# IQInput.net
KiCad netlist of a schematic drawn in EAGLE
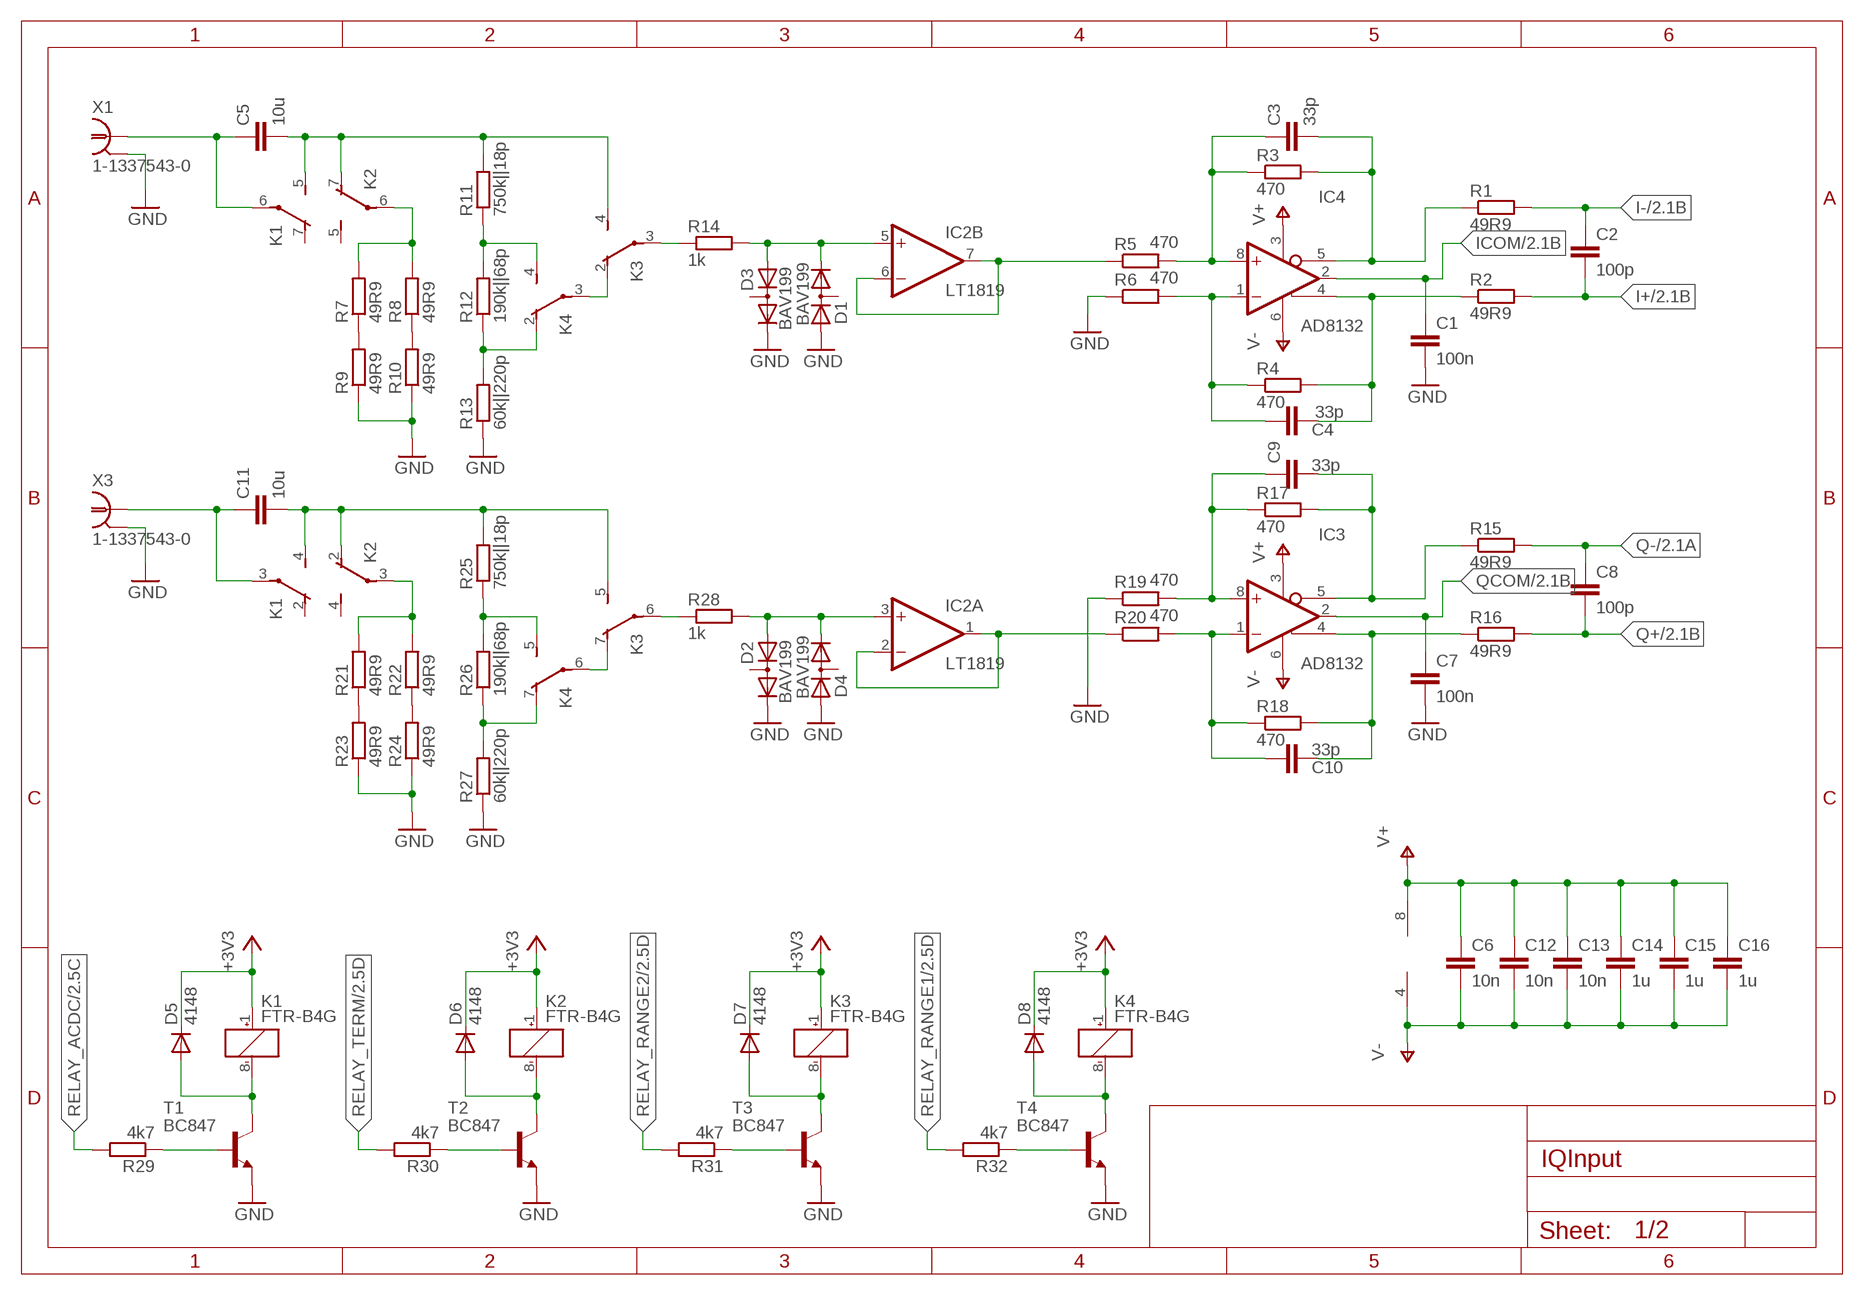
[diagram p0: schematic, sheet 1]
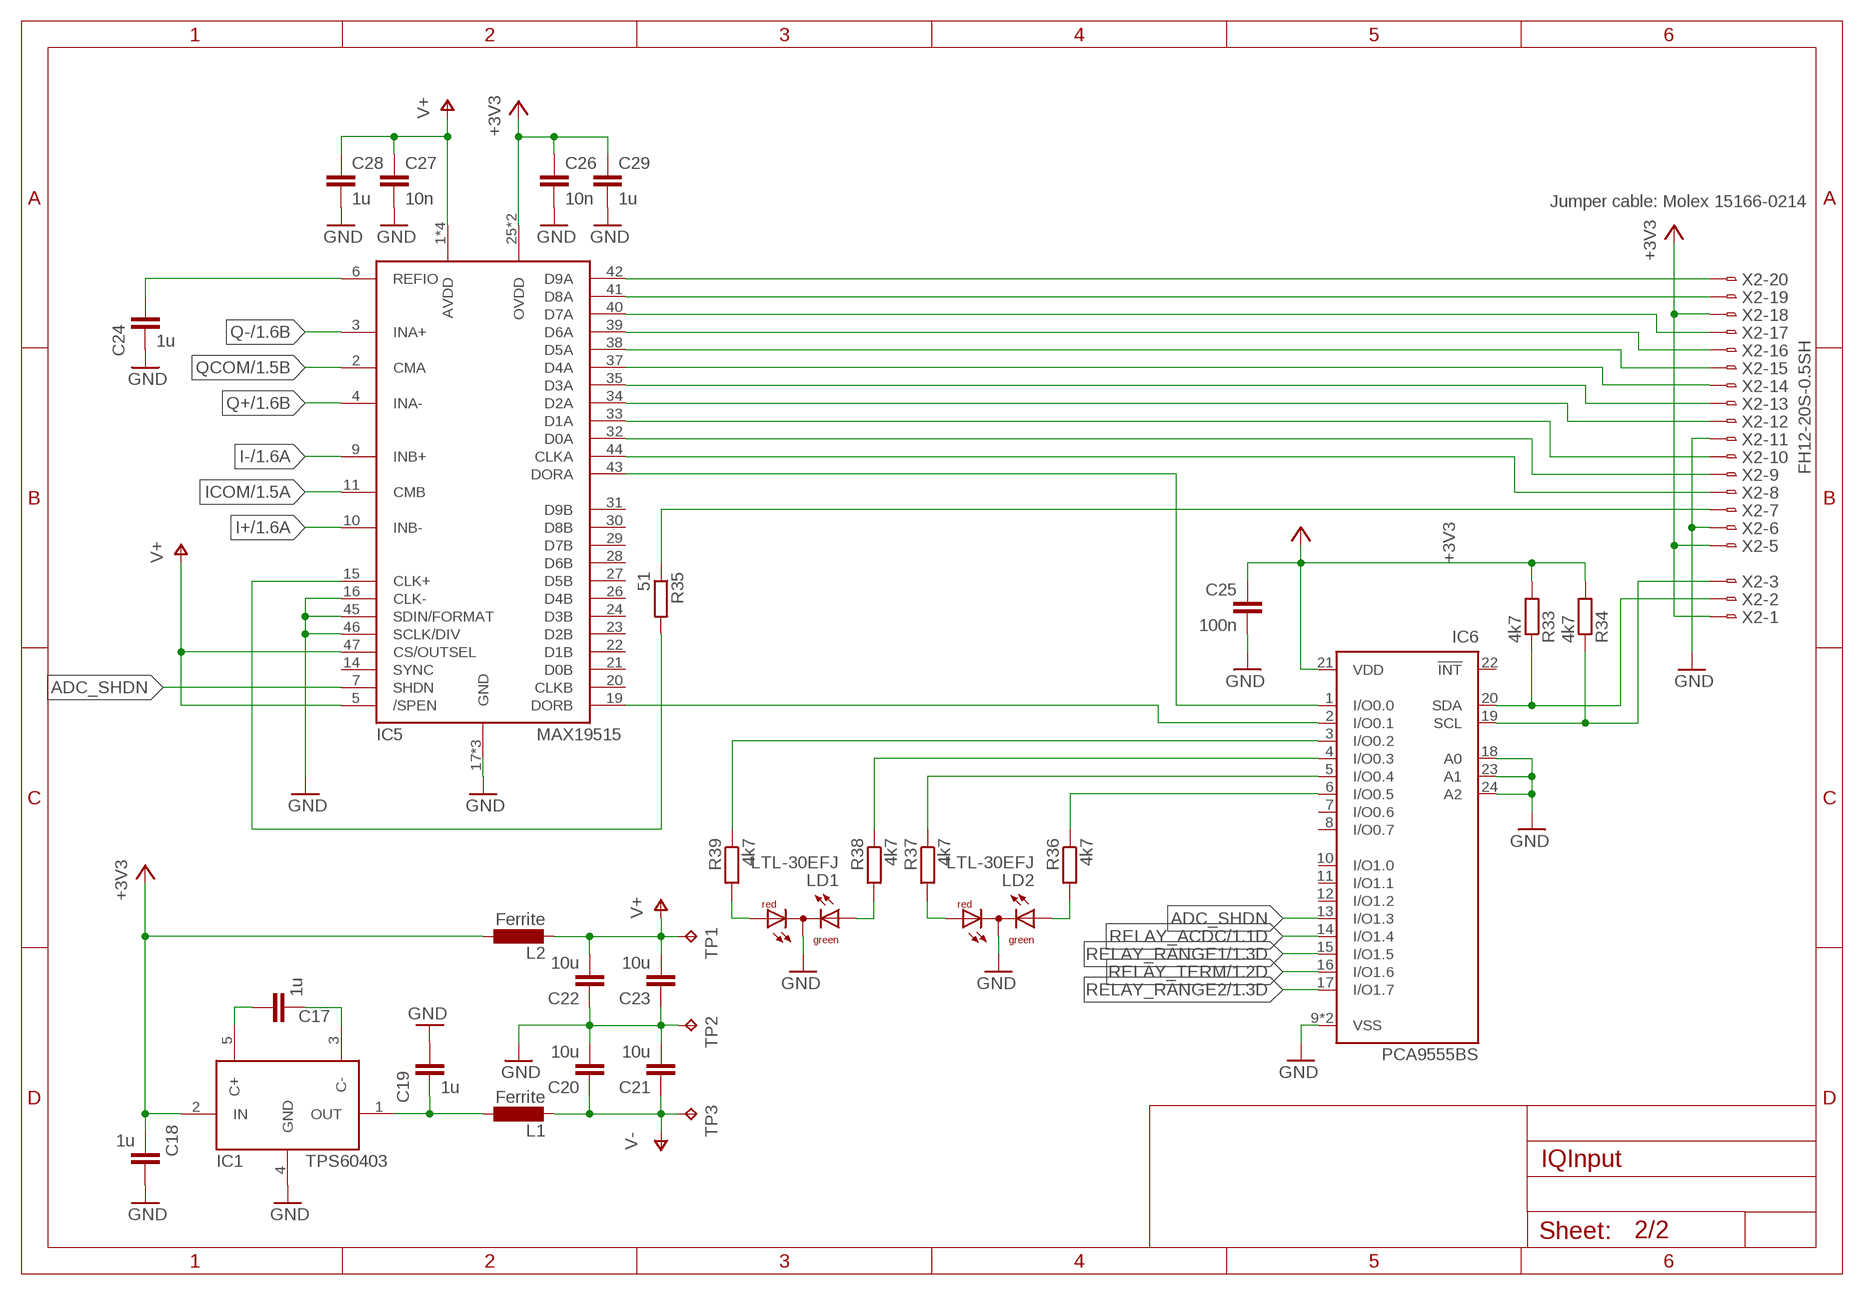
[diagram p1: schematic, sheet 2]

(export (version "E")
  (design (tool "Eeschema 10.0.6"))
  (components
    (comp (ref "C17")
      (value "1u")
      (footprint "eagle-import:C0603")
      (libsource (lib "eagle-import") (part "C-EUC0603"))
    )
    (comp (ref "C18")
      (value "1u")
      (footprint "eagle-import:C0603")
      (libsource (lib "eagle-import") (part "C-EUC0603"))
    )
    (comp (ref "C19")
      (value "1u")
      (footprint "eagle-import:C0603")
      (libsource (lib "eagle-import") (part "C-EUC0603"))
    )
    (comp (ref "C20")
      (value "10u")
      (footprint "eagle-import:C1206")
      (libsource (lib "eagle-import") (part "C-EUC1206"))
    )
    (comp (ref "C21")
      (value "10u")
      (footprint "eagle-import:C1206")
      (libsource (lib "eagle-import") (part "C-EUC1206"))
    )
    (comp (ref "C22")
      (value "10u")
      (footprint "eagle-import:C1206")
      (libsource (lib "eagle-import") (part "C-EUC1206"))
    )
    (comp (ref "C23")
      (value "10u")
      (footprint "eagle-import:C1206")
      (libsource (lib "eagle-import") (part "C-EUC1206"))
    )
    (comp (ref "C24")
      (value "1u")
      (footprint "eagle-import:C0603")
      (libsource (lib "eagle-import") (part "C-EUC0603"))
    )
    (comp (ref "C25")
      (value "100n")
      (footprint "eagle-import:C0603")
      (libsource (lib "eagle-import") (part "C-EUC0603"))
    )
    (comp (ref "C26")
      (value "10n")
      (footprint "eagle-import:C0603")
      (libsource (lib "eagle-import") (part "C-EUC0603"))
    )
    (comp (ref "C27")
      (value "10n")
      (footprint "eagle-import:C0603")
      (libsource (lib "eagle-import") (part "C-EUC0603"))
    )
    (comp (ref "C28")
      (value "1u")
      (footprint "eagle-import:C0603")
      (libsource (lib "eagle-import") (part "C-EUC0603"))
    )
    (comp (ref "C29")
      (value "1u")
      (footprint "eagle-import:C0603")
      (libsource (lib "eagle-import") (part "C-EUC0603"))
    )
    (comp (ref "IC1")
      (value "TPS60403")
      (footprint "eagle-import:SOT23-5")
      (libsource (lib "eagle-import") (part "TPS60403"))
    )
    (comp (ref "IC5")
      (value "MAX19515")
      (footprint "eagle-import:QFN50P700X700X75-49T550N")
      (libsource (lib "eagle-import") (part "MAX19515"))
    )
    (comp (ref "IC6")
      (value "PCA9555BS")
      (footprint "eagle-import:HVQFN24")
      (fields (field (name "MPN") "PCA9555BS,118"))
      (libsource (lib "eagle-import") (part "PCA9555BS"))
    )
    (comp (ref "L1")
      (value "Ferrite")
      (footprint "eagle-import:L2012C")
      (libsource (lib "eagle-import") (part "L-EUL2012C"))
    )
    (comp (ref "L2")
      (value "Ferrite")
      (footprint "eagle-import:L2012C")
      (libsource (lib "eagle-import") (part "L-EUL2012C"))
    )
    (comp (ref "LD1")
      (value "LTL-30EFJ")
      (footprint "eagle-import:DUOLED-C-5MM")
      (libsource (lib "eagle-import") (part "DUOLED-RG-C"))
    )
    (comp (ref "LD2")
      (value "LTL-30EFJ")
      (footprint "eagle-import:DUOLED-C-5MM")
      (libsource (lib "eagle-import") (part "DUOLED-RG-C"))
    )
    (comp (ref "R33")
      (value "4k7")
      (footprint "eagle-import:R0603")
      (libsource (lib "eagle-import") (part "R-EU_R0603"))
    )
    (comp (ref "R34")
      (value "4k7")
      (footprint "eagle-import:R0603")
      (libsource (lib "eagle-import") (part "R-EU_R0603"))
    )
    (comp (ref "R35")
      (value "51")
      (footprint "eagle-import:R0603")
      (libsource (lib "eagle-import") (part "R-EU_R0603"))
    )
    (comp (ref "R36")
      (value "4k7")
      (footprint "eagle-import:R0603")
      (libsource (lib "eagle-import") (part "R-EU_R0603"))
    )
    (comp (ref "R37")
      (value "4k7")
      (footprint "eagle-import:R0603")
      (libsource (lib "eagle-import") (part "R-EU_R0603"))
    )
    (comp (ref "R38")
      (value "4k7")
      (footprint "eagle-import:R0603")
      (libsource (lib "eagle-import") (part "R-EU_R0603"))
    )
    (comp (ref "R39")
      (value "4k7")
      (footprint "eagle-import:R0603")
      (libsource (lib "eagle-import") (part "R-EU_R0603"))
    )
    (comp (ref "TP1")
      (value "TPTP15R")
      (footprint "eagle-import:TP15R")
      (libsource (lib "eagle-import") (part "TPTP15R"))
    )
    (comp (ref "TP2")
      (value "TPTP15R")
      (footprint "eagle-import:TP15R")
      (libsource (lib "eagle-import") (part "TPTP15R"))
    )
    (comp (ref "TP3")
      (value "TPTP15R")
      (footprint "eagle-import:TP15R")
      (libsource (lib "eagle-import") (part "TPTP15R"))
    )
    (comp (ref "X2")
      (value "FH12-20S-0.5SH")
      (footprint "eagle-import:FH12-20S-0.5SH")
      (fields (field (name "MPN") "FH12-20S-0.5SH(55)"))
      (libsource (lib "eagle-import") (part "FH12-20S-0.5SH"))
    )
    (comp (ref "C1")
      (value "100n")
      (footprint "eagle-import:C0603")
      (libsource (lib "eagle-import") (part "C-EUC0603"))
    )
    (comp (ref "C2")
      (value "100p")
      (footprint "eagle-import:C0603")
      (libsource (lib "eagle-import") (part "C-EUC0603"))
    )
    (comp (ref "C3")
      (value "33p")
      (footprint "eagle-import:C0603")
      (libsource (lib "eagle-import") (part "C-EUC0603"))
    )
    (comp (ref "C4")
      (value "33p")
      (footprint "eagle-import:C0603")
      (libsource (lib "eagle-import") (part "C-EUC0603"))
    )
    (comp (ref "C5")
      (value "10u")
      (footprint "eagle-import:C1206")
      (libsource (lib "eagle-import") (part "C-EUC1206"))
    )
    (comp (ref "C6")
      (value "10n")
      (footprint "eagle-import:C0603")
      (libsource (lib "eagle-import") (part "C-EUC0603"))
    )
    (comp (ref "C7")
      (value "100n")
      (footprint "eagle-import:C0603")
      (libsource (lib "eagle-import") (part "C-EUC0603"))
    )
    (comp (ref "C8")
      (value "100p")
      (footprint "eagle-import:C0603")
      (libsource (lib "eagle-import") (part "C-EUC0603"))
    )
    (comp (ref "C9")
      (value "33p")
      (footprint "eagle-import:C0603")
      (libsource (lib "eagle-import") (part "C-EUC0603"))
    )
    (comp (ref "C10")
      (value "33p")
      (footprint "eagle-import:C0603")
      (libsource (lib "eagle-import") (part "C-EUC0603"))
    )
    (comp (ref "C11")
      (value "10u")
      (footprint "eagle-import:C1206")
      (libsource (lib "eagle-import") (part "C-EUC1206"))
    )
    (comp (ref "C12")
      (value "10n")
      (footprint "eagle-import:C0603")
      (libsource (lib "eagle-import") (part "C-EUC0603"))
    )
    (comp (ref "C13")
      (value "10n")
      (footprint "eagle-import:C0603")
      (libsource (lib "eagle-import") (part "C-EUC0603"))
    )
    (comp (ref "C14")
      (value "1u")
      (footprint "eagle-import:C0603")
      (libsource (lib "eagle-import") (part "C-EUC0603"))
    )
    (comp (ref "C15")
      (value "1u")
      (footprint "eagle-import:C0603")
      (libsource (lib "eagle-import") (part "C-EUC0603"))
    )
    (comp (ref "C16")
      (value "1u")
      (footprint "eagle-import:C0603")
      (libsource (lib "eagle-import") (part "C-EUC0603"))
    )
    (comp (ref "D1")
      (value "BAV199")
      (footprint "eagle-import:SOT23")
      (libsource (lib "eagle-import") (part "BAV199"))
    )
    (comp (ref "D2")
      (value "BAV199")
      (footprint "eagle-import:SOT23")
      (libsource (lib "eagle-import") (part "BAV199"))
    )
    (comp (ref "D3")
      (value "BAV199")
      (footprint "eagle-import:SOT23")
      (libsource (lib "eagle-import") (part "BAV199"))
    )
    (comp (ref "D4")
      (value "BAV199")
      (footprint "eagle-import:SOT23")
      (libsource (lib "eagle-import") (part "BAV199"))
    )
    (comp (ref "D5")
      (value "4148")
      (footprint "eagle-import:MINIMELF")
      (libsource (lib "eagle-import") (part "DIODE-MINIMELF"))
    )
    (comp (ref "D6")
      (value "4148")
      (footprint "eagle-import:MINIMELF")
      (libsource (lib "eagle-import") (part "DIODE-MINIMELF"))
    )
    (comp (ref "D7")
      (value "4148")
      (footprint "eagle-import:MINIMELF")
      (libsource (lib "eagle-import") (part "DIODE-MINIMELF"))
    )
    (comp (ref "D8")
      (value "4148")
      (footprint "eagle-import:MINIMELF")
      (libsource (lib "eagle-import") (part "DIODE-MINIMELF"))
    )
    (comp (ref "IC2")
      (value "LT1819")
      (footprint "eagle-import:SO08")
      (libsource (lib "eagle-import") (part "LM358D"))
    )
    (comp (ref "IC3")
      (value "AD8132")
      (footprint "eagle-import:MSOP8")
      (libsource (lib "eagle-import") (part "AD8132"))
    )
    (comp (ref "IC4")
      (value "AD8132")
      (footprint "eagle-import:MSOP8")
      (libsource (lib "eagle-import") (part "AD8132"))
    )
    (comp (ref "K1")
      (value "FTR-B4G")
      (footprint "eagle-import:FTR-B4G")
      (libsource (lib "eagle-import") (part "FTR-B4G"))
    )
    (comp (ref "K2")
      (value "FTR-B4G")
      (footprint "eagle-import:FTR-B4G")
      (libsource (lib "eagle-import") (part "FTR-B4G"))
    )
    (comp (ref "K3")
      (value "FTR-B4G")
      (footprint "eagle-import:FTR-B4G")
      (libsource (lib "eagle-import") (part "FTR-B4G"))
    )
    (comp (ref "K4")
      (value "FTR-B4G")
      (footprint "eagle-import:FTR-B4G")
      (libsource (lib "eagle-import") (part "FTR-B4G"))
    )
    (comp (ref "R1")
      (value "49R9")
      (footprint "eagle-import:R0603")
      (libsource (lib "eagle-import") (part "R-EU_R0603"))
    )
    (comp (ref "R2")
      (value "49R9")
      (footprint "eagle-import:R0603")
      (libsource (lib "eagle-import") (part "R-EU_R0603"))
    )
    (comp (ref "R3")
      (value "470")
      (footprint "eagle-import:R0603")
      (libsource (lib "eagle-import") (part "R-EU_R0603"))
    )
    (comp (ref "R4")
      (value "470")
      (footprint "eagle-import:R0603")
      (libsource (lib "eagle-import") (part "R-EU_R0603"))
    )
    (comp (ref "R5")
      (value "470")
      (footprint "eagle-import:R0603")
      (libsource (lib "eagle-import") (part "R-EU_R0603"))
    )
    (comp (ref "R6")
      (value "470")
      (footprint "eagle-import:R0603")
      (libsource (lib "eagle-import") (part "R-EU_R0603"))
    )
    (comp (ref "R7")
      (value "49R9")
      (footprint "eagle-import:R1206")
      (libsource (lib "eagle-import") (part "resistor_R-EU_R1206"))
    )
    (comp (ref "R8")
      (value "49R9")
      (footprint "eagle-import:R1206")
      (libsource (lib "eagle-import") (part "resistor_R-EU_R1206"))
    )
    (comp (ref "R9")
      (value "49R9")
      (footprint "eagle-import:R1206")
      (libsource (lib "eagle-import") (part "resistor_R-EU_R1206"))
    )
    (comp (ref "R10")
      (value "49R9")
      (footprint "eagle-import:R1206")
      (libsource (lib "eagle-import") (part "resistor_R-EU_R1206"))
    )
    (comp (ref "R11")
      (value "750k||18p")
      (footprint "eagle-import:R0603")
      (libsource (lib "eagle-import") (part "R-EU_R0603"))
    )
    (comp (ref "R12")
      (value "190k||68p")
      (footprint "eagle-import:R0603")
      (libsource (lib "eagle-import") (part "R-EU_R0603"))
    )
    (comp (ref "R13")
      (value "60k||220p")
      (footprint "eagle-import:R0603")
      (libsource (lib "eagle-import") (part "R-EU_R0603"))
    )
    (comp (ref "R14")
      (value "1k")
      (footprint "eagle-import:R0603")
      (libsource (lib "eagle-import") (part "R-EU_R0603"))
    )
    (comp (ref "R15")
      (value "49R9")
      (footprint "eagle-import:R0603")
      (libsource (lib "eagle-import") (part "R-EU_R0603"))
    )
    (comp (ref "R16")
      (value "49R9")
      (footprint "eagle-import:R0603")
      (libsource (lib "eagle-import") (part "R-EU_R0603"))
    )
    (comp (ref "R17")
      (value "470")
      (footprint "eagle-import:R0603")
      (libsource (lib "eagle-import") (part "R-EU_R0603"))
    )
    (comp (ref "R18")
      (value "470")
      (footprint "eagle-import:R0603")
      (libsource (lib "eagle-import") (part "R-EU_R0603"))
    )
    (comp (ref "R19")
      (value "470")
      (footprint "eagle-import:R0603")
      (libsource (lib "eagle-import") (part "R-EU_R0603"))
    )
    (comp (ref "R20")
      (value "470")
      (footprint "eagle-import:R0603")
      (libsource (lib "eagle-import") (part "R-EU_R0603"))
    )
    (comp (ref "R21")
      (value "49R9")
      (footprint "eagle-import:R1206")
      (libsource (lib "eagle-import") (part "resistor_R-EU_R1206"))
    )
    (comp (ref "R22")
      (value "49R9")
      (footprint "eagle-import:R1206")
      (libsource (lib "eagle-import") (part "resistor_R-EU_R1206"))
    )
    (comp (ref "R23")
      (value "49R9")
      (footprint "eagle-import:R1206")
      (libsource (lib "eagle-import") (part "resistor_R-EU_R1206"))
    )
    (comp (ref "R24")
      (value "49R9")
      (footprint "eagle-import:R1206")
      (libsource (lib "eagle-import") (part "resistor_R-EU_R1206"))
    )
    (comp (ref "R25")
      (value "750k||18p")
      (footprint "eagle-import:R0603")
      (libsource (lib "eagle-import") (part "R-EU_R0603"))
    )
    (comp (ref "R26")
      (value "190k||68p")
      (footprint "eagle-import:R0603")
      (libsource (lib "eagle-import") (part "R-EU_R0603"))
    )
    (comp (ref "R27")
      (value "60k||220p")
      (footprint "eagle-import:R0603")
      (libsource (lib "eagle-import") (part "R-EU_R0603"))
    )
    (comp (ref "R28")
      (value "1k")
      (footprint "eagle-import:R0603")
      (libsource (lib "eagle-import") (part "R-EU_R0603"))
    )
    (comp (ref "R29")
      (value "4k7")
      (footprint "eagle-import:R0603")
      (libsource (lib "eagle-import") (part "R-EU_R0603"))
    )
    (comp (ref "R30")
      (value "4k7")
      (footprint "eagle-import:R0603")
      (libsource (lib "eagle-import") (part "R-EU_R0603"))
    )
    (comp (ref "R31")
      (value "4k7")
      (footprint "eagle-import:R0603")
      (libsource (lib "eagle-import") (part "R-EU_R0603"))
    )
    (comp (ref "R32")
      (value "4k7")
      (footprint "eagle-import:R0603")
      (libsource (lib "eagle-import") (part "R-EU_R0603"))
    )
    (comp (ref "T1")
      (value "BC847")
      (footprint "eagle-import:SOT23")
      (libsource (lib "eagle-import") (part "BC847"))
    )
    (comp (ref "T2")
      (value "BC847")
      (footprint "eagle-import:SOT23")
      (libsource (lib "eagle-import") (part "BC847"))
    )
    (comp (ref "T3")
      (value "BC847")
      (footprint "eagle-import:SOT23")
      (libsource (lib "eagle-import") (part "BC847"))
    )
    (comp (ref "T4")
      (value "BC847")
      (footprint "eagle-import:SOT23")
      (libsource (lib "eagle-import") (part "BC847"))
    )
    (comp (ref "X1")
      (value "1-1337543-0")
      (footprint "eagle-import:AMP_227161")
      (fields (field (name "MF") "TYCO ELECTRONICS") (field (name "MPN") "1-227161-7"))
      (libsource (lib "eagle-import") (part "?2271611--7"))
    )
    (comp (ref "X3")
      (value "1-1337543-0")
      (footprint "eagle-import:AMP_227161")
      (fields (field (name "MF") "TYCO ELECTRONICS") (field (name "MPN") "1-227161-7"))
      (libsource (lib "eagle-import") (part "?2271611--7"))
    )
  )
  (nets
    (net (code "1") (name "+3V3") (class "Default")
      (node (ref "C18") (pin "2") (pinfunction "2_2") (pintype "passive"))
      (node (ref "C25") (pin "1") (pinfunction "1_1") (pintype "passive"))
      (node (ref "C26") (pin "1") (pinfunction "1_1") (pintype "passive"))
      (node (ref "C29") (pin "1") (pinfunction "1_1") (pintype "passive"))
      (node (ref "D5") (pin "C") (pinfunction "C_C") (pintype "passive"))
      (node (ref "D6") (pin "C") (pinfunction "C_C") (pintype "passive"))
      (node (ref "D7") (pin "C") (pinfunction "C_C") (pintype "passive"))
      (node (ref "D8") (pin "C") (pinfunction "C_C") (pintype "passive"))
      (node (ref "IC1") (pin "2") (pinfunction "IN_2") (pintype "bidirectional"))
      (node (ref "IC5") (pin "25") (pinfunction "OVDD_25") (pintype "bidirectional"))
      (node (ref "IC5") (pin "36") (pinfunction "OVDD_36") (pintype "bidirectional"))
      (node (ref "IC6") (pin "21") (pinfunction "VDD_21") (pintype "power_in"))
      (node (ref "K1") (pin "1") (pinfunction "+_1") (pintype "passive"))
      (node (ref "K2") (pin "1") (pinfunction "+_1") (pintype "passive"))
      (node (ref "K3") (pin "1") (pinfunction "+_1") (pintype "passive"))
      (node (ref "K4") (pin "1") (pinfunction "+_1") (pintype "passive"))
      (node (ref "L2") (pin "1") (pinfunction "1_1") (pintype "passive"))
      (node (ref "R33") (pin "2") (pinfunction "2_2") (pintype "passive"))
      (node (ref "R34") (pin "2") (pinfunction "2_2") (pintype "passive"))
      (node (ref "X2") (pin "1") (pinfunction "1_1") (pintype "passive"))
      (node (ref "X2") (pin "18") (pinfunction "1_18") (pintype "passive"))
      (node (ref "X2") (pin "5") (pinfunction "1_5") (pintype "passive"))
    )
    (net (code "2") (name "ADC_SHDN") (class "Default")
      (node (ref "IC5") (pin "7") (pinfunction "SHDN_7") (pintype "bidirectional"))
      (node (ref "IC6") (pin "13") (pinfunction "I/O1.3_13") (pintype "bidirectional"))
    )
    (net (code "3") (name "GND") (class "Default")
      (node (ref "C1") (pin "2") (pinfunction "2_2") (pintype "passive"))
      (node (ref "C18") (pin "1") (pinfunction "1_1") (pintype "passive"))
      (node (ref "C19") (pin "1") (pinfunction "1_1") (pintype "passive"))
      (node (ref "C20") (pin "2") (pinfunction "2_2") (pintype "passive"))
      (node (ref "C21") (pin "2") (pinfunction "2_2") (pintype "passive"))
      (node (ref "C22") (pin "1") (pinfunction "1_1") (pintype "passive"))
      (node (ref "C23") (pin "1") (pinfunction "1_1") (pintype "passive"))
      (node (ref "C24") (pin "2") (pinfunction "2_2") (pintype "passive"))
      (node (ref "C25") (pin "2") (pinfunction "2_2") (pintype "passive"))
      (node (ref "C26") (pin "2") (pinfunction "2_2") (pintype "passive"))
      (node (ref "C27") (pin "2") (pinfunction "2_2") (pintype "passive"))
      (node (ref "C28") (pin "2") (pinfunction "2_2") (pintype "passive"))
      (node (ref "C29") (pin "2") (pinfunction "2_2") (pintype "passive"))
      (node (ref "C7") (pin "2") (pinfunction "2_2") (pintype "passive"))
      (node (ref "D1") (pin "1") (pinfunction "A_1") (pintype "passive"))
      (node (ref "D2") (pin "2") (pinfunction "C_2") (pintype "passive"))
      (node (ref "D3") (pin "2") (pinfunction "C_2") (pintype "passive"))
      (node (ref "D4") (pin "1") (pinfunction "A_1") (pintype "passive"))
      (node (ref "IC1") (pin "4") (pinfunction "GND_4") (pintype "bidirectional"))
      (node (ref "IC5") (pin "16") (pinfunction "CLK-_16") (pintype "bidirectional"))
      (node (ref "IC5") (pin "17") (pinfunction "GND_17") (pintype "bidirectional"))
      (node (ref "IC5") (pin "18") (pinfunction "GND_18") (pintype "bidirectional"))
      (node (ref "IC5") (pin "45") (pinfunction "SDIN/FORMAT_45") (pintype "bidirectional"))
      (node (ref "IC5") (pin "46") (pinfunction "SCLK/DIV_46") (pintype "bidirectional"))
      (node (ref "IC5") (pin "49") (pinfunction "GND_49") (pintype "bidirectional"))
      (node (ref "IC6") (pin "18") (pinfunction "A0_18") (pintype "input"))
      (node (ref "IC6") (pin "23") (pinfunction "A1_23") (pintype "input"))
      (node (ref "IC6") (pin "24") (pinfunction "A2_24") (pintype "input"))
      (node (ref "IC6") (pin "9") (pinfunction "VSS_9") (pintype "power_in"))
      (node (ref "IC6") (pin "TH") (pinfunction "VSS_TH") (pintype "power_in"))
      (node (ref "LD1") (pin "C") (pinfunction "C_C") (pintype "passive"))
      (node (ref "LD2") (pin "C") (pinfunction "C_C") (pintype "passive"))
      (node (ref "R10") (pin "1") (pinfunction "1_1") (pintype "passive"))
      (node (ref "R13") (pin "1") (pinfunction "1_1") (pintype "passive"))
      (node (ref "R19") (pin "1") (pinfunction "1_1") (pintype "passive"))
      (node (ref "R23") (pin "1") (pinfunction "1_1") (pintype "passive"))
      (node (ref "R24") (pin "1") (pinfunction "1_1") (pintype "passive"))
      (node (ref "R27") (pin "1") (pinfunction "1_1") (pintype "passive"))
      (node (ref "R6") (pin "1") (pinfunction "1_1") (pintype "passive"))
      (node (ref "R9") (pin "1") (pinfunction "1_1") (pintype "passive"))
      (node (ref "T1") (pin "2") (pinfunction "E_2") (pintype "passive"))
      (node (ref "T2") (pin "2") (pinfunction "E_2") (pintype "passive"))
      (node (ref "T3") (pin "2") (pinfunction "E_2") (pintype "passive"))
      (node (ref "T4") (pin "2") (pinfunction "E_2") (pintype "passive"))
      (node (ref "TP2") (pin "TP") (pinfunction "TP_TP") (pintype "input"))
      (node (ref "X1") (pin "2") (pinfunction "2_2") (pintype "passive"))
      (node (ref "X2") (pin "11") (pinfunction "1_11") (pintype "passive"))
      (node (ref "X2") (pin "6") (pinfunction "1_6") (pintype "passive"))
      (node (ref "X3") (pin "2") (pinfunction "2_2") (pintype "passive"))
    )
    (net (code "4") (name "I+") (class "Default")
      (node (ref "C2") (pin "2") (pinfunction "2_2") (pintype "passive"))
      (node (ref "IC5") (pin "10") (pinfunction "INB-_10") (pintype "bidirectional"))
      (node (ref "R2") (pin "2") (pinfunction "2_2") (pintype "passive"))
    )
    (net (code "5") (name "I-") (class "Default")
      (node (ref "C2") (pin "1") (pinfunction "1_1") (pintype "passive"))
      (node (ref "IC5") (pin "9") (pinfunction "INB+_9") (pintype "bidirectional"))
      (node (ref "R1") (pin "2") (pinfunction "2_2") (pintype "passive"))
    )
    (net (code "6") (name "ICOM") (class "Default")
      (node (ref "C1") (pin "1") (pinfunction "1_1") (pintype "passive"))
      (node (ref "IC4") (pin "2") (pinfunction "VOCM_2") (pintype "output"))
      (node (ref "IC5") (pin "11") (pinfunction "CMB_11") (pintype "bidirectional"))
    )
    (net (code "7") (name "Net-(D1-C)") (class "Default")
      (node (ref "D1") (pin "2") (pinfunction "C_2") (pintype "passive"))
      (node (ref "D3") (pin "1") (pinfunction "A_1") (pintype "passive"))
      (node (ref "IC2") (pin "5") (pinfunction "+IN_5") (pintype "input"))
      (node (ref "R14") (pin "2") (pinfunction "2_2") (pintype "passive"))
    )
    (net (code "8") (name "Net-(D2-A)") (class "Default")
      (node (ref "D2") (pin "1") (pinfunction "A_1") (pintype "passive"))
      (node (ref "D4") (pin "2") (pinfunction "C_2") (pintype "passive"))
      (node (ref "IC2") (pin "3") (pinfunction "+IN_3") (pintype "input"))
      (node (ref "R28") (pin "2") (pinfunction "2_2") (pintype "passive"))
    )
    (net (code "9") (name "Net-(IC1-C+)") (class "Default")
      (node (ref "C17") (pin "1") (pinfunction "1_1") (pintype "passive"))
      (node (ref "IC1") (pin "5") (pinfunction "C+_5") (pintype "bidirectional"))
    )
    (net (code "10") (name "Net-(IC1-C-)") (class "Default")
      (node (ref "C17") (pin "2") (pinfunction "2_2") (pintype "passive"))
      (node (ref "IC1") (pin "3") (pinfunction "C-_3") (pintype "bidirectional"))
    )
    (net (code "11") (name "Net-(IC1-OUT)") (class "Default")
      (node (ref "C19") (pin "2") (pinfunction "2_2") (pintype "passive"))
      (node (ref "IC1") (pin "1") (pinfunction "OUT_1") (pintype "bidirectional"))
      (node (ref "L1") (pin "1") (pinfunction "1_1") (pintype "passive"))
    )
    (net (code "12") (name "Net-(IC2A--IN)") (class "Default")
      (node (ref "IC2") (pin "1") (pinfunction "OUT_1") (pintype "output"))
      (node (ref "IC2") (pin "2") (pinfunction "-IN_2") (pintype "input"))
      (node (ref "R20") (pin "1") (pinfunction "1_1") (pintype "passive"))
    )
    (net (code "13") (name "Net-(IC2B--IN)") (class "Default")
      (node (ref "IC2") (pin "6") (pinfunction "-IN_6") (pintype "input"))
      (node (ref "IC2") (pin "7") (pinfunction "OUT_7") (pintype "output"))
      (node (ref "R5") (pin "1") (pinfunction "1_1") (pintype "passive"))
    )
    (net (code "14") (name "Net-(IC3-+IN)") (class "Default")
      (node (ref "C9") (pin "1") (pinfunction "1_1") (pintype "passive"))
      (node (ref "IC3") (pin "8") (pinfunction "+IN_8") (pintype "input"))
      (node (ref "R17") (pin "1") (pinfunction "1_1") (pintype "passive"))
      (node (ref "R19") (pin "2") (pinfunction "2_2") (pintype "passive"))
    )
    (net (code "15") (name "Net-(IC3-+OUT)") (class "Default")
      (node (ref "C10") (pin "2") (pinfunction "2_2") (pintype "passive"))
      (node (ref "IC3") (pin "4") (pinfunction "+OUT_4") (pintype "bidirectional"))
      (node (ref "R16") (pin "1") (pinfunction "1_1") (pintype "passive"))
      (node (ref "R18") (pin "2") (pinfunction "2_2") (pintype "passive"))
    )
    (net (code "16") (name "Net-(IC3--IN)") (class "Default")
      (node (ref "C10") (pin "1") (pinfunction "1_1") (pintype "passive"))
      (node (ref "IC3") (pin "1") (pinfunction "-IN_1") (pintype "input"))
      (node (ref "R18") (pin "1") (pinfunction "1_1") (pintype "passive"))
      (node (ref "R20") (pin "2") (pinfunction "2_2") (pintype "passive"))
    )
    (net (code "17") (name "Net-(IC3--OUT)") (class "Default")
      (node (ref "C9") (pin "2") (pinfunction "2_2") (pintype "passive"))
      (node (ref "IC3") (pin "5") (pinfunction "-OUT_5") (pintype "bidirectional"))
      (node (ref "R15") (pin "1") (pinfunction "1_1") (pintype "passive"))
      (node (ref "R17") (pin "2") (pinfunction "2_2") (pintype "passive"))
    )
    (net (code "18") (name "Net-(IC4-+IN)") (class "Default")
      (node (ref "C3") (pin "1") (pinfunction "1_1") (pintype "passive"))
      (node (ref "IC4") (pin "8") (pinfunction "+IN_8") (pintype "input"))
      (node (ref "R3") (pin "1") (pinfunction "1_1") (pintype "passive"))
      (node (ref "R5") (pin "2") (pinfunction "2_2") (pintype "passive"))
    )
    (net (code "19") (name "Net-(IC4-+OUT)") (class "Default")
      (node (ref "C4") (pin "2") (pinfunction "2_2") (pintype "passive"))
      (node (ref "IC4") (pin "4") (pinfunction "+OUT_4") (pintype "bidirectional"))
      (node (ref "R2") (pin "1") (pinfunction "1_1") (pintype "passive"))
      (node (ref "R4") (pin "2") (pinfunction "2_2") (pintype "passive"))
    )
    (net (code "20") (name "Net-(IC4--IN)") (class "Default")
      (node (ref "C4") (pin "1") (pinfunction "1_1") (pintype "passive"))
      (node (ref "IC4") (pin "1") (pinfunction "-IN_1") (pintype "input"))
      (node (ref "R4") (pin "1") (pinfunction "1_1") (pintype "passive"))
      (node (ref "R6") (pin "2") (pinfunction "2_2") (pintype "passive"))
    )
    (net (code "21") (name "Net-(IC4--OUT)") (class "Default")
      (node (ref "C3") (pin "2") (pinfunction "2_2") (pintype "passive"))
      (node (ref "IC4") (pin "5") (pinfunction "-OUT_5") (pintype "bidirectional"))
      (node (ref "R1") (pin "1") (pinfunction "1_1") (pintype "passive"))
      (node (ref "R3") (pin "2") (pinfunction "2_2") (pintype "passive"))
    )
    (net (code "22") (name "Net-(IC5-CLK+)") (class "Default")
      (node (ref "IC5") (pin "15") (pinfunction "CLK+_15") (pintype "bidirectional"))
      (node (ref "R35") (pin "2") (pinfunction "2_2") (pintype "passive"))
    )
    (net (code "23") (name "Net-(IC5-CLKA)") (class "Default")
      (node (ref "IC5") (pin "44") (pinfunction "CLKA_44") (pintype "bidirectional"))
      (node (ref "X2") (pin "8") (pinfunction "1_8") (pintype "passive"))
    )
    (net (code "24") (name "Net-(IC5-D0A)") (class "Default")
      (node (ref "IC5") (pin "32") (pinfunction "D0A_32") (pintype "bidirectional"))
      (node (ref "X2") (pin "9") (pinfunction "1_9") (pintype "passive"))
    )
    (net (code "25") (name "Net-(IC5-D1A)") (class "Default")
      (node (ref "IC5") (pin "33") (pinfunction "D1A_33") (pintype "bidirectional"))
      (node (ref "X2") (pin "10") (pinfunction "1_10") (pintype "passive"))
    )
    (net (code "26") (name "Net-(IC5-D2A)") (class "Default")
      (node (ref "IC5") (pin "34") (pinfunction "D2A_34") (pintype "bidirectional"))
      (node (ref "X2") (pin "12") (pinfunction "1_12") (pintype "passive"))
    )
    (net (code "27") (name "Net-(IC5-D3A)") (class "Default")
      (node (ref "IC5") (pin "35") (pinfunction "D3A_35") (pintype "bidirectional"))
      (node (ref "X2") (pin "13") (pinfunction "1_13") (pintype "passive"))
    )
    (net (code "28") (name "Net-(IC5-D4A)") (class "Default")
      (node (ref "IC5") (pin "37") (pinfunction "D4A_37") (pintype "bidirectional"))
      (node (ref "X2") (pin "14") (pinfunction "1_14") (pintype "passive"))
    )
    (net (code "29") (name "Net-(IC5-D5A)") (class "Default")
      (node (ref "IC5") (pin "38") (pinfunction "D5A_38") (pintype "bidirectional"))
      (node (ref "X2") (pin "15") (pinfunction "1_15") (pintype "passive"))
    )
    (net (code "30") (name "Net-(IC5-D6A)") (class "Default")
      (node (ref "IC5") (pin "39") (pinfunction "D6A_39") (pintype "bidirectional"))
      (node (ref "X2") (pin "16") (pinfunction "1_16") (pintype "passive"))
    )
    (net (code "31") (name "Net-(IC5-D7A)") (class "Default")
      (node (ref "IC5") (pin "40") (pinfunction "D7A_40") (pintype "bidirectional"))
      (node (ref "X2") (pin "17") (pinfunction "1_17") (pintype "passive"))
    )
    (net (code "32") (name "Net-(IC5-D8A)") (class "Default")
      (node (ref "IC5") (pin "41") (pinfunction "D8A_41") (pintype "bidirectional"))
      (node (ref "X2") (pin "19") (pinfunction "1_19") (pintype "passive"))
    )
    (net (code "33") (name "Net-(IC5-D9A)") (class "Default")
      (node (ref "IC5") (pin "42") (pinfunction "D9A_42") (pintype "bidirectional"))
      (node (ref "X2") (pin "20") (pinfunction "1_20") (pintype "passive"))
    )
    (net (code "34") (name "Net-(IC5-DORA)") (class "Default")
      (node (ref "IC5") (pin "43") (pinfunction "DORA_43") (pintype "bidirectional"))
      (node (ref "IC6") (pin "1") (pinfunction "I/O0.0_1") (pintype "bidirectional"))
    )
    (net (code "35") (name "Net-(IC5-DORB)") (class "Default")
      (node (ref "IC5") (pin "19") (pinfunction "DORB_19") (pintype "bidirectional"))
      (node (ref "IC6") (pin "2") (pinfunction "I/O0.1_2") (pintype "bidirectional"))
    )
    (net (code "36") (name "Net-(IC5-REFIO)") (class "Default")
      (node (ref "C24") (pin "1") (pinfunction "1_1") (pintype "passive"))
      (node (ref "IC5") (pin "6") (pinfunction "REFIO_6") (pintype "bidirectional"))
    )
    (net (code "37") (name "Net-(IC6-I{slash}O0.2)") (class "Default")
      (node (ref "IC6") (pin "3") (pinfunction "I/O0.2_3") (pintype "bidirectional"))
      (node (ref "R39") (pin "1") (pinfunction "1_1") (pintype "passive"))
    )
    (net (code "38") (name "Net-(IC6-I{slash}O0.3)") (class "Default")
      (node (ref "IC6") (pin "4") (pinfunction "I/O0.3_4") (pintype "bidirectional"))
      (node (ref "R38") (pin "1") (pinfunction "1_1") (pintype "passive"))
    )
    (net (code "39") (name "Net-(IC6-I{slash}O0.4)") (class "Default")
      (node (ref "IC6") (pin "5") (pinfunction "I/O0.4_5") (pintype "bidirectional"))
      (node (ref "R37") (pin "1") (pinfunction "1_1") (pintype "passive"))
    )
    (net (code "40") (name "Net-(IC6-I{slash}O0.5)") (class "Default")
      (node (ref "IC6") (pin "6") (pinfunction "I/O0.5_6") (pintype "bidirectional"))
      (node (ref "R36") (pin "1") (pinfunction "1_1") (pintype "passive"))
    )
    (net (code "41") (name "Net-(IC6-SCL)") (class "Default")
      (node (ref "IC6") (pin "19") (pinfunction "SCL_19") (pintype "input"))
      (node (ref "R34") (pin "1") (pinfunction "1_1") (pintype "passive"))
      (node (ref "X2") (pin "3") (pinfunction "1_3") (pintype "passive"))
    )
    (net (code "42") (name "Net-(IC6-SDA)") (class "Default")
      (node (ref "IC6") (pin "20") (pinfunction "SDA_20") (pintype "bidirectional"))
      (node (ref "R33") (pin "1") (pinfunction "1_1") (pintype "passive"))
      (node (ref "X2") (pin "2") (pinfunction "1_2") (pintype "passive"))
    )
    (net (code "43") (name "Net-(K1A-P)") (class "Default")
      (node (ref "C11") (pin "1") (pinfunction "1_1") (pintype "passive"))
      (node (ref "K1") (pin "3") (pinfunction "P_3") (pintype "passive"))
      (node (ref "X3") (pin "1") (pinfunction "1_1") (pintype "passive"))
    )
    (net (code "44") (name "Net-(K1A-S)") (class "Default")
      (node (ref "C11") (pin "2") (pinfunction "2_2") (pintype "passive"))
      (node (ref "K1") (pin "4") (pinfunction "S_4") (pintype "passive"))
      (node (ref "K2") (pin "2") (pinfunction "O_2") (pintype "passive"))
      (node (ref "K3") (pin "5") (pinfunction "S_5") (pintype "passive"))
      (node (ref "R25") (pin "2") (pinfunction "2_2") (pintype "passive"))
    )
    (net (code "45") (name "Net-(K1B-P)") (class "Default")
      (node (ref "C5") (pin "1") (pinfunction "1_1") (pintype "passive"))
      (node (ref "K1") (pin "6") (pinfunction "P_6") (pintype "passive"))
      (node (ref "X1") (pin "1") (pinfunction "1_1") (pintype "passive"))
    )
    (net (code "46") (name "Net-(K1B-S)") (class "Default")
      (node (ref "C5") (pin "2") (pinfunction "2_2") (pintype "passive"))
      (node (ref "K1") (pin "5") (pinfunction "S_5") (pintype "passive"))
      (node (ref "K2") (pin "7") (pinfunction "O_7") (pintype "passive"))
      (node (ref "K3") (pin "4") (pinfunction "S_4") (pintype "passive"))
      (node (ref "R11") (pin "2") (pinfunction "2_2") (pintype "passive"))
    )
    (net (code "47") (name "Net-(K1C--)") (class "Default")
      (node (ref "D5") (pin "A") (pinfunction "A_A") (pintype "passive"))
      (node (ref "K1") (pin "8") (pinfunction "-_8") (pintype "passive"))
      (node (ref "T1") (pin "3") (pinfunction "C_3") (pintype "passive"))
    )
    (net (code "48") (name "Net-(K2A-P)") (class "Default")
      (node (ref "K2") (pin "3") (pinfunction "P_3") (pintype "passive"))
      (node (ref "R21") (pin "2") (pinfunction "2_2") (pintype "passive"))
      (node (ref "R22") (pin "2") (pinfunction "2_2") (pintype "passive"))
    )
    (net (code "49") (name "Net-(K2B-P)") (class "Default")
      (node (ref "K2") (pin "6") (pinfunction "P_6") (pintype "passive"))
      (node (ref "R7") (pin "2") (pinfunction "2_2") (pintype "passive"))
      (node (ref "R8") (pin "2") (pinfunction "2_2") (pintype "passive"))
    )
    (net (code "50") (name "Net-(K2C--)") (class "Default")
      (node (ref "D6") (pin "A") (pinfunction "A_A") (pintype "passive"))
      (node (ref "K2") (pin "8") (pinfunction "-_8") (pintype "passive"))
      (node (ref "T2") (pin "3") (pinfunction "C_3") (pintype "passive"))
    )
    (net (code "51") (name "Net-(K3A-O)") (class "Default")
      (node (ref "K3") (pin "2") (pinfunction "O_2") (pintype "passive"))
      (node (ref "K4") (pin "3") (pinfunction "P_3") (pintype "passive"))
    )
    (net (code "52") (name "Net-(K3A-P)") (class "Default")
      (node (ref "K3") (pin "3") (pinfunction "P_3") (pintype "passive"))
      (node (ref "R14") (pin "1") (pinfunction "1_1") (pintype "passive"))
    )
    (net (code "53") (name "Net-(K3B-O)") (class "Default")
      (node (ref "K3") (pin "7") (pinfunction "O_7") (pintype "passive"))
      (node (ref "K4") (pin "6") (pinfunction "P_6") (pintype "passive"))
    )
    (net (code "54") (name "Net-(K3B-P)") (class "Default")
      (node (ref "K3") (pin "6") (pinfunction "P_6") (pintype "passive"))
      (node (ref "R28") (pin "1") (pinfunction "1_1") (pintype "passive"))
    )
    (net (code "55") (name "Net-(K3C--)") (class "Default")
      (node (ref "D7") (pin "A") (pinfunction "A_A") (pintype "passive"))
      (node (ref "K3") (pin "8") (pinfunction "-_8") (pintype "passive"))
      (node (ref "T3") (pin "3") (pinfunction "C_3") (pintype "passive"))
    )
    (net (code "56") (name "Net-(K4A-O)") (class "Default")
      (node (ref "K4") (pin "2") (pinfunction "O_2") (pintype "passive"))
      (node (ref "R12") (pin "1") (pinfunction "1_1") (pintype "passive"))
      (node (ref "R13") (pin "2") (pinfunction "2_2") (pintype "passive"))
    )
    (net (code "57") (name "Net-(K4A-S)") (class "Default")
      (node (ref "K4") (pin "4") (pinfunction "S_4") (pintype "passive"))
      (node (ref "R11") (pin "1") (pinfunction "1_1") (pintype "passive"))
      (node (ref "R12") (pin "2") (pinfunction "2_2") (pintype "passive"))
    )
    (net (code "58") (name "Net-(K4B-O)") (class "Default")
      (node (ref "K4") (pin "7") (pinfunction "O_7") (pintype "passive"))
      (node (ref "R26") (pin "1") (pinfunction "1_1") (pintype "passive"))
      (node (ref "R27") (pin "2") (pinfunction "2_2") (pintype "passive"))
    )
    (net (code "59") (name "Net-(K4B-S)") (class "Default")
      (node (ref "K4") (pin "5") (pinfunction "S_5") (pintype "passive"))
      (node (ref "R25") (pin "1") (pinfunction "1_1") (pintype "passive"))
      (node (ref "R26") (pin "2") (pinfunction "2_2") (pintype "passive"))
    )
    (net (code "60") (name "Net-(K4C--)") (class "Default")
      (node (ref "D8") (pin "A") (pinfunction "A_A") (pintype "passive"))
      (node (ref "K4") (pin "8") (pinfunction "-_8") (pintype "passive"))
      (node (ref "T4") (pin "3") (pinfunction "C_3") (pintype "passive"))
    )
    (net (code "61") (name "Net-(LD1-AG)") (class "Default")
      (node (ref "LD1") (pin "AX") (pinfunction "AG_AX") (pintype "passive"))
      (node (ref "R38") (pin "2") (pinfunction "2_2") (pintype "passive"))
    )
    (net (code "62") (name "Net-(LD1-PadAR)") (class "Default")
      (node (ref "LD1") (pin "AR") (pinfunction "AR_AR") (pintype "passive"))
      (node (ref "R39") (pin "2") (pinfunction "2_2") (pintype "passive"))
    )
    (net (code "63") (name "Net-(LD2-AG)") (class "Default")
      (node (ref "LD2") (pin "AX") (pinfunction "AG_AX") (pintype "passive"))
      (node (ref "R36") (pin "2") (pinfunction "2_2") (pintype "passive"))
    )
    (net (code "64") (name "Net-(LD2-PadAR)") (class "Default")
      (node (ref "LD2") (pin "AR") (pinfunction "AR_AR") (pintype "passive"))
      (node (ref "R37") (pin "2") (pinfunction "2_2") (pintype "passive"))
    )
    (net (code "65") (name "Net-(R7-Pad1)") (class "Default")
      (node (ref "R7") (pin "1") (pinfunction "1_1") (pintype "passive"))
      (node (ref "R9") (pin "2") (pinfunction "2_2") (pintype "passive"))
    )
    (net (code "66") (name "Net-(R10-Pad2)") (class "Default")
      (node (ref "R10") (pin "2") (pinfunction "2_2") (pintype "passive"))
      (node (ref "R8") (pin "1") (pinfunction "1_1") (pintype "passive"))
    )
    (net (code "67") (name "Net-(R21-Pad1)") (class "Default")
      (node (ref "R21") (pin "1") (pinfunction "1_1") (pintype "passive"))
      (node (ref "R23") (pin "2") (pinfunction "2_2") (pintype "passive"))
    )
    (net (code "68") (name "Net-(R22-Pad1)") (class "Default")
      (node (ref "R22") (pin "1") (pinfunction "1_1") (pintype "passive"))
      (node (ref "R24") (pin "2") (pinfunction "2_2") (pintype "passive"))
    )
    (net (code "69") (name "Net-(T1-B)") (class "Default")
      (node (ref "R29") (pin "1") (pinfunction "1_1") (pintype "passive"))
      (node (ref "T1") (pin "1") (pinfunction "B_1") (pintype "passive"))
    )
    (net (code "70") (name "Net-(T2-B)") (class "Default")
      (node (ref "R30") (pin "1") (pinfunction "1_1") (pintype "passive"))
      (node (ref "T2") (pin "1") (pinfunction "B_1") (pintype "passive"))
    )
    (net (code "71") (name "Net-(T3-B)") (class "Default")
      (node (ref "R31") (pin "1") (pinfunction "1_1") (pintype "passive"))
      (node (ref "T3") (pin "1") (pinfunction "B_1") (pintype "passive"))
    )
    (net (code "72") (name "Net-(T4-B)") (class "Default")
      (node (ref "R32") (pin "1") (pinfunction "1_1") (pintype "passive"))
      (node (ref "T4") (pin "1") (pinfunction "B_1") (pintype "passive"))
    )
    (net (code "73") (name "Net-(X2R-1)") (class "Default")
      (node (ref "R35") (pin "1") (pinfunction "1_1") (pintype "passive"))
      (node (ref "X2") (pin "7") (pinfunction "1_7") (pintype "passive"))
    )
    (net (code "74") (name "Q+") (class "Default")
      (node (ref "C8") (pin "2") (pinfunction "2_2") (pintype "passive"))
      (node (ref "IC5") (pin "4") (pinfunction "INA-_4") (pintype "bidirectional"))
      (node (ref "R16") (pin "2") (pinfunction "2_2") (pintype "passive"))
    )
    (net (code "75") (name "Q-") (class "Default")
      (node (ref "C8") (pin "1") (pinfunction "1_1") (pintype "passive"))
      (node (ref "IC5") (pin "3") (pinfunction "INA+_3") (pintype "bidirectional"))
      (node (ref "R15") (pin "2") (pinfunction "2_2") (pintype "passive"))
    )
    (net (code "76") (name "QCOM") (class "Default")
      (node (ref "C7") (pin "1") (pinfunction "1_1") (pintype "passive"))
      (node (ref "IC3") (pin "2") (pinfunction "VOCM_2") (pintype "output"))
      (node (ref "IC5") (pin "2") (pinfunction "CMA_2") (pintype "bidirectional"))
    )
    (net (code "77") (name "RELAY_ACDC") (class "Default")
      (node (ref "IC6") (pin "14") (pinfunction "I/O1.4_14") (pintype "bidirectional"))
      (node (ref "R29") (pin "2") (pinfunction "2_2") (pintype "passive"))
    )
    (net (code "78") (name "RELAY_RANGE1") (class "Default")
      (node (ref "IC6") (pin "15") (pinfunction "I/O1.5_15") (pintype "bidirectional"))
      (node (ref "R32") (pin "2") (pinfunction "2_2") (pintype "passive"))
    )
    (net (code "79") (name "RELAY_RANGE2") (class "Default")
      (node (ref "IC6") (pin "17") (pinfunction "I/O1.7_17") (pintype "bidirectional"))
      (node (ref "R31") (pin "2") (pinfunction "2_2") (pintype "passive"))
    )
    (net (code "80") (name "RELAY_TERM") (class "Default")
      (node (ref "IC6") (pin "16") (pinfunction "I/O1.6_16") (pintype "bidirectional"))
      (node (ref "R30") (pin "2") (pinfunction "2_2") (pintype "passive"))
    )
    (net (code "81") (name "V+") (class "Default")
      (node (ref "C12") (pin "1") (pinfunction "1_1") (pintype "passive"))
      (node (ref "C13") (pin "1") (pinfunction "1_1") (pintype "passive"))
      (node (ref "C14") (pin "1") (pinfunction "1_1") (pintype "passive"))
      (node (ref "C15") (pin "1") (pinfunction "1_1") (pintype "passive"))
      (node (ref "C16") (pin "1") (pinfunction "1_1") (pintype "passive"))
      (node (ref "C22") (pin "2") (pinfunction "2_2") (pintype "passive"))
      (node (ref "C23") (pin "2") (pinfunction "2_2") (pintype "passive"))
      (node (ref "C27") (pin "1") (pinfunction "1_1") (pintype "passive"))
      (node (ref "C28") (pin "1") (pinfunction "1_1") (pintype "passive"))
      (node (ref "C6") (pin "1") (pinfunction "1_1") (pintype "passive"))
      (node (ref "IC2") (pin "8") (pinfunction "V+_8") (pintype "power_in"))
      (node (ref "IC3") (pin "3") (pinfunction "V+_3") (pintype "power_in"))
      (node (ref "IC4") (pin "3") (pinfunction "V+_3") (pintype "power_in"))
      (node (ref "IC5") (pin "1") (pinfunction "AVDD_1") (pintype "bidirectional"))
      (node (ref "IC5") (pin "12") (pinfunction "AVDD_12") (pintype "bidirectional"))
      (node (ref "IC5") (pin "13") (pinfunction "AVDD_13") (pintype "bidirectional"))
      (node (ref "IC5") (pin "47") (pinfunction "CS/OUTSEL_47") (pintype "bidirectional"))
      (node (ref "IC5") (pin "48") (pinfunction "AVDD_48") (pintype "bidirectional"))
      (node (ref "IC5") (pin "5") (pinfunction "/SPEN_5") (pintype "bidirectional"))
      (node (ref "L2") (pin "2") (pinfunction "2_2") (pintype "passive"))
      (node (ref "TP1") (pin "TP") (pinfunction "TP_TP") (pintype "input"))
    )
    (net (code "82") (name "V-") (class "Default")
      (node (ref "C12") (pin "2") (pinfunction "2_2") (pintype "passive"))
      (node (ref "C13") (pin "2") (pinfunction "2_2") (pintype "passive"))
      (node (ref "C14") (pin "2") (pinfunction "2_2") (pintype "passive"))
      (node (ref "C15") (pin "2") (pinfunction "2_2") (pintype "passive"))
      (node (ref "C16") (pin "2") (pinfunction "2_2") (pintype "passive"))
      (node (ref "C20") (pin "1") (pinfunction "1_1") (pintype "passive"))
      (node (ref "C21") (pin "1") (pinfunction "1_1") (pintype "passive"))
      (node (ref "C6") (pin "2") (pinfunction "2_2") (pintype "passive"))
      (node (ref "IC2") (pin "4") (pinfunction "V-_4") (pintype "power_in"))
      (node (ref "IC3") (pin "6") (pinfunction "V-_6") (pintype "power_in"))
      (node (ref "IC4") (pin "6") (pinfunction "V-_6") (pintype "power_in"))
      (node (ref "L1") (pin "2") (pinfunction "2_2") (pintype "passive"))
      (node (ref "TP3") (pin "TP") (pinfunction "TP_TP") (pintype "input"))
    )
    (net (code "83") (name "unconnected-(D1-AC-Pad3)") (class "Default")
      (node (ref "D1") (pin "3") (pinfunction "AC_3") (pintype "passive"))
    )
    (net (code "84") (name "unconnected-(D2-AC-Pad3)") (class "Default")
      (node (ref "D2") (pin "3") (pinfunction "AC_3") (pintype "passive"))
    )
    (net (code "85") (name "unconnected-(D3-AC-Pad3)") (class "Default")
      (node (ref "D3") (pin "3") (pinfunction "AC_3") (pintype "passive"))
    )
    (net (code "86") (name "unconnected-(D4-AC-Pad3)") (class "Default")
      (node (ref "D4") (pin "3") (pinfunction "AC_3") (pintype "passive"))
    )
    (net (code "87") (name "unconnected-(IC5-CLKB-Pad20)") (class "Default")
      (node (ref "IC5") (pin "20") (pinfunction "CLKB_20") (pintype "bidirectional"))
    )
    (net (code "88") (name "unconnected-(IC5-D0B-Pad21)") (class "Default")
      (node (ref "IC5") (pin "21") (pinfunction "D0B_21") (pintype "bidirectional"))
    )
    (net (code "89") (name "unconnected-(IC5-D1B-Pad22)") (class "Default")
      (node (ref "IC5") (pin "22") (pinfunction "D1B_22") (pintype "bidirectional"))
    )
    (net (code "90") (name "unconnected-(IC5-D2B-Pad23)") (class "Default")
      (node (ref "IC5") (pin "23") (pinfunction "D2B_23") (pintype "bidirectional"))
    )
    (net (code "91") (name "unconnected-(IC5-D3B-Pad24)") (class "Default")
      (node (ref "IC5") (pin "24") (pinfunction "D3B_24") (pintype "bidirectional"))
    )
    (net (code "92") (name "unconnected-(IC5-D4B-Pad26)") (class "Default")
      (node (ref "IC5") (pin "26") (pinfunction "D4B_26") (pintype "bidirectional"))
    )
    (net (code "93") (name "unconnected-(IC5-D5B-Pad27)") (class "Default")
      (node (ref "IC5") (pin "27") (pinfunction "D5B_27") (pintype "bidirectional"))
    )
    (net (code "94") (name "unconnected-(IC5-D6B-Pad28)") (class "Default")
      (node (ref "IC5") (pin "28") (pinfunction "D6B_28") (pintype "bidirectional"))
    )
    (net (code "95") (name "unconnected-(IC5-D7B-Pad29)") (class "Default")
      (node (ref "IC5") (pin "29") (pinfunction "D7B_29") (pintype "bidirectional"))
    )
    (net (code "96") (name "unconnected-(IC5-D8B-Pad30)") (class "Default")
      (node (ref "IC5") (pin "30") (pinfunction "D8B_30") (pintype "bidirectional"))
    )
    (net (code "97") (name "unconnected-(IC5-D9B-Pad31)") (class "Default")
      (node (ref "IC5") (pin "31") (pinfunction "D9B_31") (pintype "bidirectional"))
    )
    (net (code "98") (name "unconnected-(IC5-SYNC-Pad14)") (class "Default")
      (node (ref "IC5") (pin "14") (pinfunction "SYNC_14") (pintype "bidirectional"))
    )
    (net (code "99") (name "unconnected-(IC6-I{slash}O0.6-Pad7)") (class "Default")
      (node (ref "IC6") (pin "7") (pinfunction "I/O0.6_7") (pintype "bidirectional"))
    )
    (net (code "100") (name "unconnected-(IC6-I{slash}O0.7-Pad8)") (class "Default")
      (node (ref "IC6") (pin "8") (pinfunction "I/O0.7_8") (pintype "bidirectional"))
    )
    (net (code "101") (name "unconnected-(IC6-I{slash}O1.0-Pad10)") (class "Default")
      (node (ref "IC6") (pin "10") (pinfunction "I/O1.0_10") (pintype "bidirectional"))
    )
    (net (code "102") (name "unconnected-(IC6-I{slash}O1.1-Pad11)") (class "Default")
      (node (ref "IC6") (pin "11") (pinfunction "I/O1.1_11") (pintype "bidirectional"))
    )
    (net (code "103") (name "unconnected-(IC6-I{slash}O1.2-Pad12)") (class "Default")
      (node (ref "IC6") (pin "12") (pinfunction "I/O1.2_12") (pintype "bidirectional"))
    )
    (net (code "104") (name "unconnected-(IC6-~{INT}-Pad22)") (class "Default")
      (node (ref "IC6") (pin "22") (pinfunction "~{INT}_22") (pintype "output"))
    )
    (net (code "105") (name "unconnected-(K1A-O-Pad2)") (class "Default")
      (node (ref "K1") (pin "2") (pinfunction "O_2") (pintype "passive"))
    )
    (net (code "106") (name "unconnected-(K1B-O-Pad7)") (class "Default")
      (node (ref "K1") (pin "7") (pinfunction "O_7") (pintype "passive"))
    )
    (net (code "107") (name "unconnected-(K2A-S-Pad4)") (class "Default")
      (node (ref "K2") (pin "4") (pinfunction "S_4") (pintype "passive"))
    )
    (net (code "108") (name "unconnected-(K2B-S-Pad5)") (class "Default")
      (node (ref "K2") (pin "5") (pinfunction "S_5") (pintype "passive"))
    )
  )
)
